# powerreducer.net
KiCad netlist of a schematic drawn in EAGLE
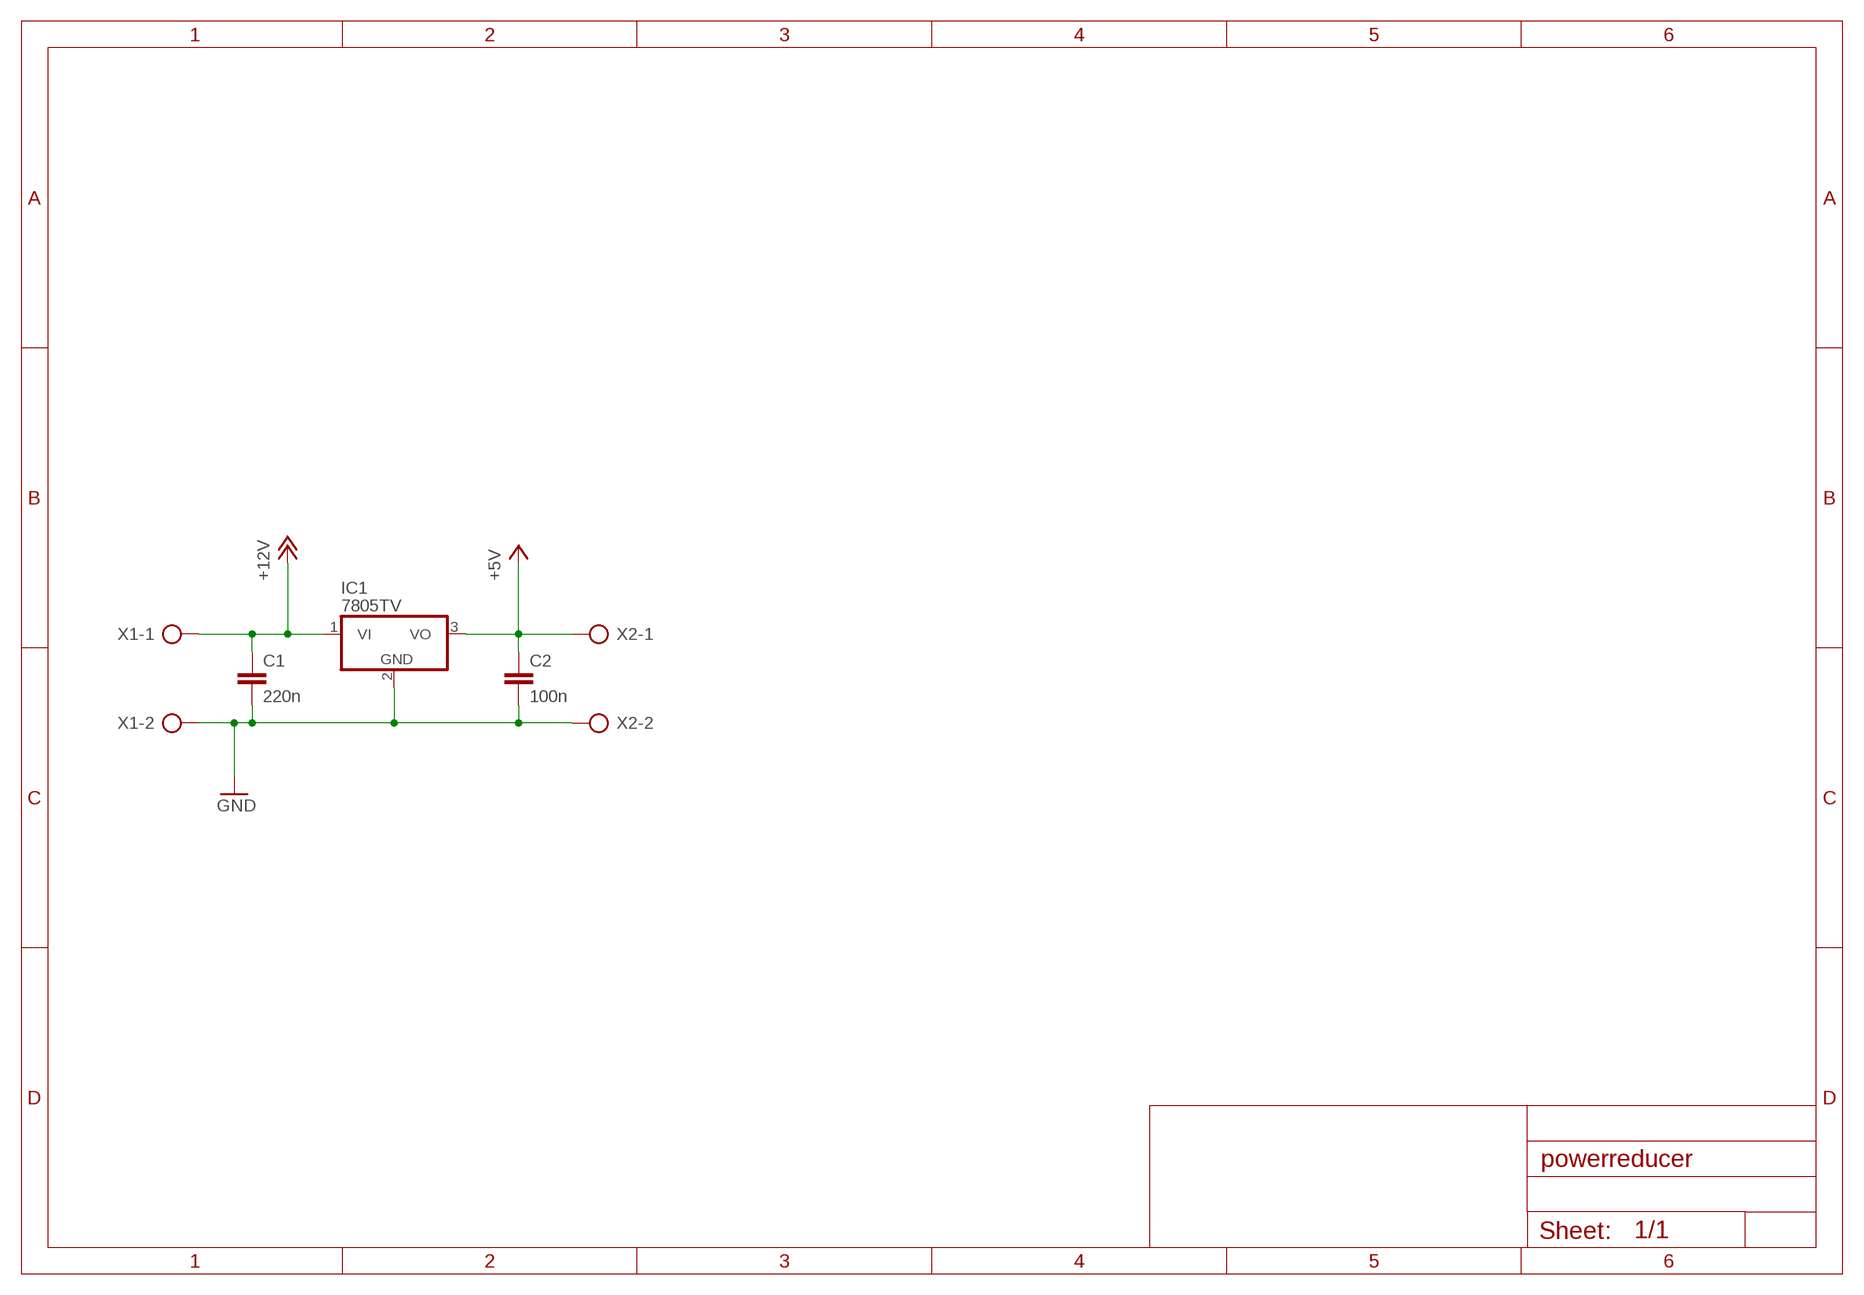
[diagram p0: schematic, sheet 1]

(export (version "E")
  (design (tool "Eeschema 10.0.6"))
  (components
    (comp (ref "C1")
      (value "220n")
      (footprint "eagle-import:C050-025X075")
      (libsource (lib "eagle-import") (part "C-EU050-025X075"))
    )
    (comp (ref "C2")
      (value "100n")
      (footprint "eagle-import:C050-025X075")
      (libsource (lib "eagle-import") (part "C-EU050-025X075"))
    )
    (comp (ref "IC1")
      (value "7805TV")
      (footprint "eagle-import:TO220V")
      (libsource (lib "eagle-import") (part "78TV05"))
    )
    (comp (ref "X1")
      (value "AK300/2")
      (footprint "eagle-import:AK300_2")
      (libsource (lib "eagle-import") (part "AK300/2"))
    )
    (comp (ref "X2")
      (value "AK300/2")
      (footprint "eagle-import:AK300_2")
      (libsource (lib "eagle-import") (part "AK300/2"))
    )
  )
  (nets
    (net (code "1") (name "+5V") (class "Default")
      (node (ref "C2") (pin "1") (pinfunction "1_1") (pintype "passive"))
      (node (ref "IC1") (pin "3") (pinfunction "VO_3") (pintype "passive"))
      (node (ref "X2") (pin "1") (pinfunction "KL_1") (pintype "passive"))
    )
    (net (code "2") (name "+12V") (class "Default")
      (node (ref "C1") (pin "1") (pinfunction "1_1") (pintype "passive"))
      (node (ref "IC1") (pin "1") (pinfunction "VI_1") (pintype "input"))
      (node (ref "X1") (pin "1") (pinfunction "KL_1") (pintype "passive"))
    )
    (net (code "3") (name "GND") (class "Default")
      (node (ref "C1") (pin "2") (pinfunction "2_2") (pintype "passive"))
      (node (ref "C2") (pin "2") (pinfunction "2_2") (pintype "passive"))
      (node (ref "IC1") (pin "2") (pinfunction "GND_2") (pintype "passive"))
      (node (ref "X1") (pin "2") (pinfunction "KL_2") (pintype "passive"))
      (node (ref "X2") (pin "2") (pinfunction "KL_2") (pintype "passive"))
    )
  )
)
